# IR_Sensor.net
KiCad netlist of a schematic drawn in EAGLE
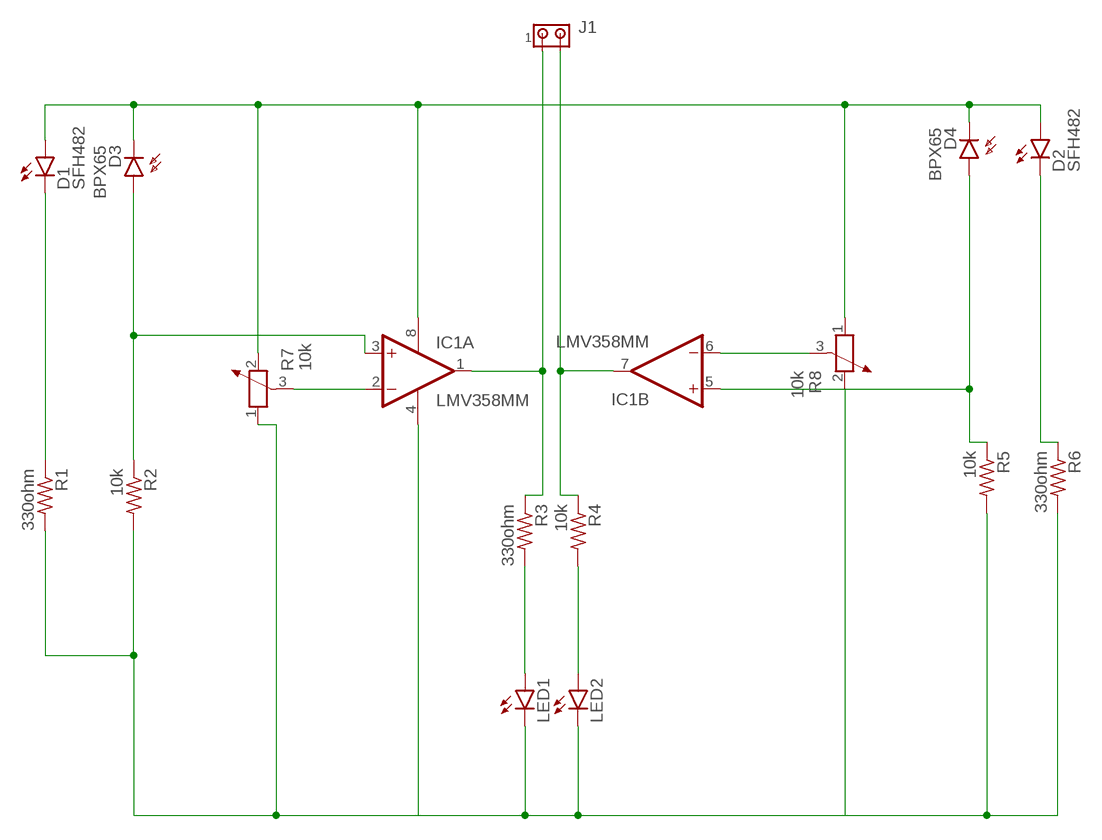
[diagram p0: schematic, sheet 1]

(export (version "E")
  (design (tool "Eeschema 10.0.6"))
  (components
    (comp (ref "D1")
      (value "SFH482")
      (footprint "eagle-import:SFH482")
      (libsource (lib "eagle-import") (part "SFH482"))
    )
    (comp (ref "D2")
      (value "SFH482")
      (footprint "eagle-import:SFH482")
      (libsource (lib "eagle-import") (part "SFH482"))
    )
    (comp (ref "D3")
      (value "BPX65")
      (footprint "eagle-import:BPX65")
      (fields (field (name "MPN") "BPX65."))
      (libsource (lib "eagle-import") (part "BPX65"))
    )
    (comp (ref "D4")
      (value "BPX65")
      (footprint "eagle-import:BPX65")
      (fields (field (name "MPN") "BPX65."))
      (libsource (lib "eagle-import") (part "BPX65"))
    )
    (comp (ref "IC1")
      (value "LMV358MM")
      (footprint "eagle-import:MSOP08")
      (libsource (lib "eagle-import") (part "LMV358?MM"))
    )
    (comp (ref "J1")
      (value "MTA02-100")
      (footprint "eagle-import:10X02MTA")
      (libsource (lib "eagle-import") (part "MTA02-100"))
    )
    (comp (ref "LED1")
      (value "LED3MM")
      (footprint "eagle-import:LED3MM")
      (libsource (lib "eagle-import") (part "LED3MM"))
    )
    (comp (ref "LED2")
      (value "LED3MM")
      (footprint "eagle-import:LED3MM")
      (libsource (lib "eagle-import") (part "LED3MM"))
    )
    (comp (ref "R1")
      (value "330ohm")
      (footprint "eagle-import:0207_10")
      (libsource (lib "eagle-import") (part "R-US_0207/10"))
    )
    (comp (ref "R2")
      (value "10k")
      (footprint "eagle-import:0207_10")
      (libsource (lib "eagle-import") (part "R-US_0207/10"))
    )
    (comp (ref "R3")
      (value "330ohm")
      (footprint "eagle-import:0207_10")
      (libsource (lib "eagle-import") (part "R-US_0207/10"))
    )
    (comp (ref "R4")
      (value "10k")
      (footprint "eagle-import:0207_10")
      (libsource (lib "eagle-import") (part "R-US_0207/10"))
    )
    (comp (ref "R5")
      (value "10k")
      (footprint "eagle-import:0207_10")
      (libsource (lib "eagle-import") (part "R-US_0207/10"))
    )
    (comp (ref "R6")
      (value "330ohm")
      (footprint "eagle-import:0207_10")
      (libsource (lib "eagle-import") (part "R-US_0207/10"))
    )
    (comp (ref "R7")
      (value "10k")
      (footprint "eagle-import:PT-10")
      (libsource (lib "eagle-import") (part "POTENTIOMETER_PT-10"))
    )
    (comp (ref "R8")
      (value "10k")
      (footprint "eagle-import:PT-10")
      (libsource (lib "eagle-import") (part "POTENTIOMETER_PT-10"))
    )
  )
  (nets
    (net (code "1") (name "Net-(D1-C)") (class "Default")
      (node (ref "D1") (pin "K") (pinfunction "C_K") (pintype "passive"))
      (node (ref "R1") (pin "1") (pinfunction "1_1") (pintype "passive"))
    )
    (net (code "2") (name "Net-(D2-C)") (class "Default")
      (node (ref "D2") (pin "K") (pinfunction "C_K") (pintype "passive"))
      (node (ref "R6") (pin "1") (pinfunction "1_1") (pintype "passive"))
    )
    (net (code "3") (name "Net-(D3-C)") (class "Default")
      (node (ref "D1") (pin "A") (pinfunction "A_A") (pintype "passive"))
      (node (ref "D2") (pin "A") (pinfunction "A_A") (pintype "passive"))
      (node (ref "D3") (pin "K") (pinfunction "C_K") (pintype "passive"))
      (node (ref "D4") (pin "K") (pinfunction "C_K") (pintype "passive"))
      (node (ref "IC1") (pin "8") (pinfunction "V+_8") (pintype "power_in"))
      (node (ref "R7") (pin "2") (pinfunction "2_2") (pintype "passive"))
      (node (ref "R8") (pin "1") (pinfunction "1_1") (pintype "passive"))
    )
    (net (code "4") (name "Net-(IC1A-+IN)") (class "Default")
      (node (ref "D3") (pin "A") (pinfunction "A_A") (pintype "passive"))
      (node (ref "IC1") (pin "3") (pinfunction "+IN_3") (pintype "input"))
      (node (ref "R2") (pin "1") (pinfunction "1_1") (pintype "passive"))
    )
    (net (code "5") (name "Net-(IC1A--IN)") (class "Default")
      (node (ref "IC1") (pin "2") (pinfunction "-IN_2") (pintype "input"))
      (node (ref "R7") (pin "3") (pinfunction "3_3") (pintype "passive"))
    )
    (net (code "6") (name "Net-(IC1A-OUT)") (class "Default")
      (node (ref "IC1") (pin "1") (pinfunction "OUT_1") (pintype "output"))
      (node (ref "J1") (pin "1") (pinfunction "1_1") (pintype "passive"))
      (node (ref "R3") (pin "1") (pinfunction "1_1") (pintype "passive"))
    )
    (net (code "7") (name "Net-(IC1B-+IN)") (class "Default")
      (node (ref "D4") (pin "A") (pinfunction "A_A") (pintype "passive"))
      (node (ref "IC1") (pin "5") (pinfunction "+IN_5") (pintype "input"))
      (node (ref "R5") (pin "1") (pinfunction "1_1") (pintype "passive"))
    )
    (net (code "8") (name "Net-(IC1B--IN)") (class "Default")
      (node (ref "IC1") (pin "6") (pinfunction "-IN_6") (pintype "input"))
      (node (ref "R8") (pin "3") (pinfunction "3_3") (pintype "passive"))
    )
    (net (code "9") (name "Net-(IC1B-OUT)") (class "Default")
      (node (ref "IC1") (pin "7") (pinfunction "OUT_7") (pintype "output"))
      (node (ref "J1") (pin "2") (pinfunction "2_2") (pintype "passive"))
      (node (ref "R4") (pin "1") (pinfunction "1_1") (pintype "passive"))
    )
    (net (code "10") (name "Net-(IC1C-V-)") (class "Default")
      (node (ref "IC1") (pin "4") (pinfunction "V-_4") (pintype "power_in"))
      (node (ref "LED1") (pin "K") (pinfunction "C_K") (pintype "passive"))
      (node (ref "LED2") (pin "K") (pinfunction "C_K") (pintype "passive"))
      (node (ref "R1") (pin "2") (pinfunction "2_2") (pintype "passive"))
      (node (ref "R2") (pin "2") (pinfunction "2_2") (pintype "passive"))
      (node (ref "R5") (pin "2") (pinfunction "2_2") (pintype "passive"))
      (node (ref "R6") (pin "2") (pinfunction "2_2") (pintype "passive"))
      (node (ref "R7") (pin "1") (pinfunction "1_1") (pintype "passive"))
      (node (ref "R8") (pin "2") (pinfunction "2_2") (pintype "passive"))
    )
    (net (code "11") (name "Net-(LED1-PadA)") (class "Default")
      (node (ref "LED1") (pin "A") (pinfunction "A_A") (pintype "passive"))
      (node (ref "R3") (pin "2") (pinfunction "2_2") (pintype "passive"))
    )
    (net (code "12") (name "Net-(LED2-PadA)") (class "Default")
      (node (ref "LED2") (pin "A") (pinfunction "A_A") (pintype "passive"))
      (node (ref "R4") (pin "2") (pinfunction "2_2") (pintype "passive"))
    )
  )
)
